# Vorladeschaltung.net
KiCad netlist of a schematic drawn in EAGLE
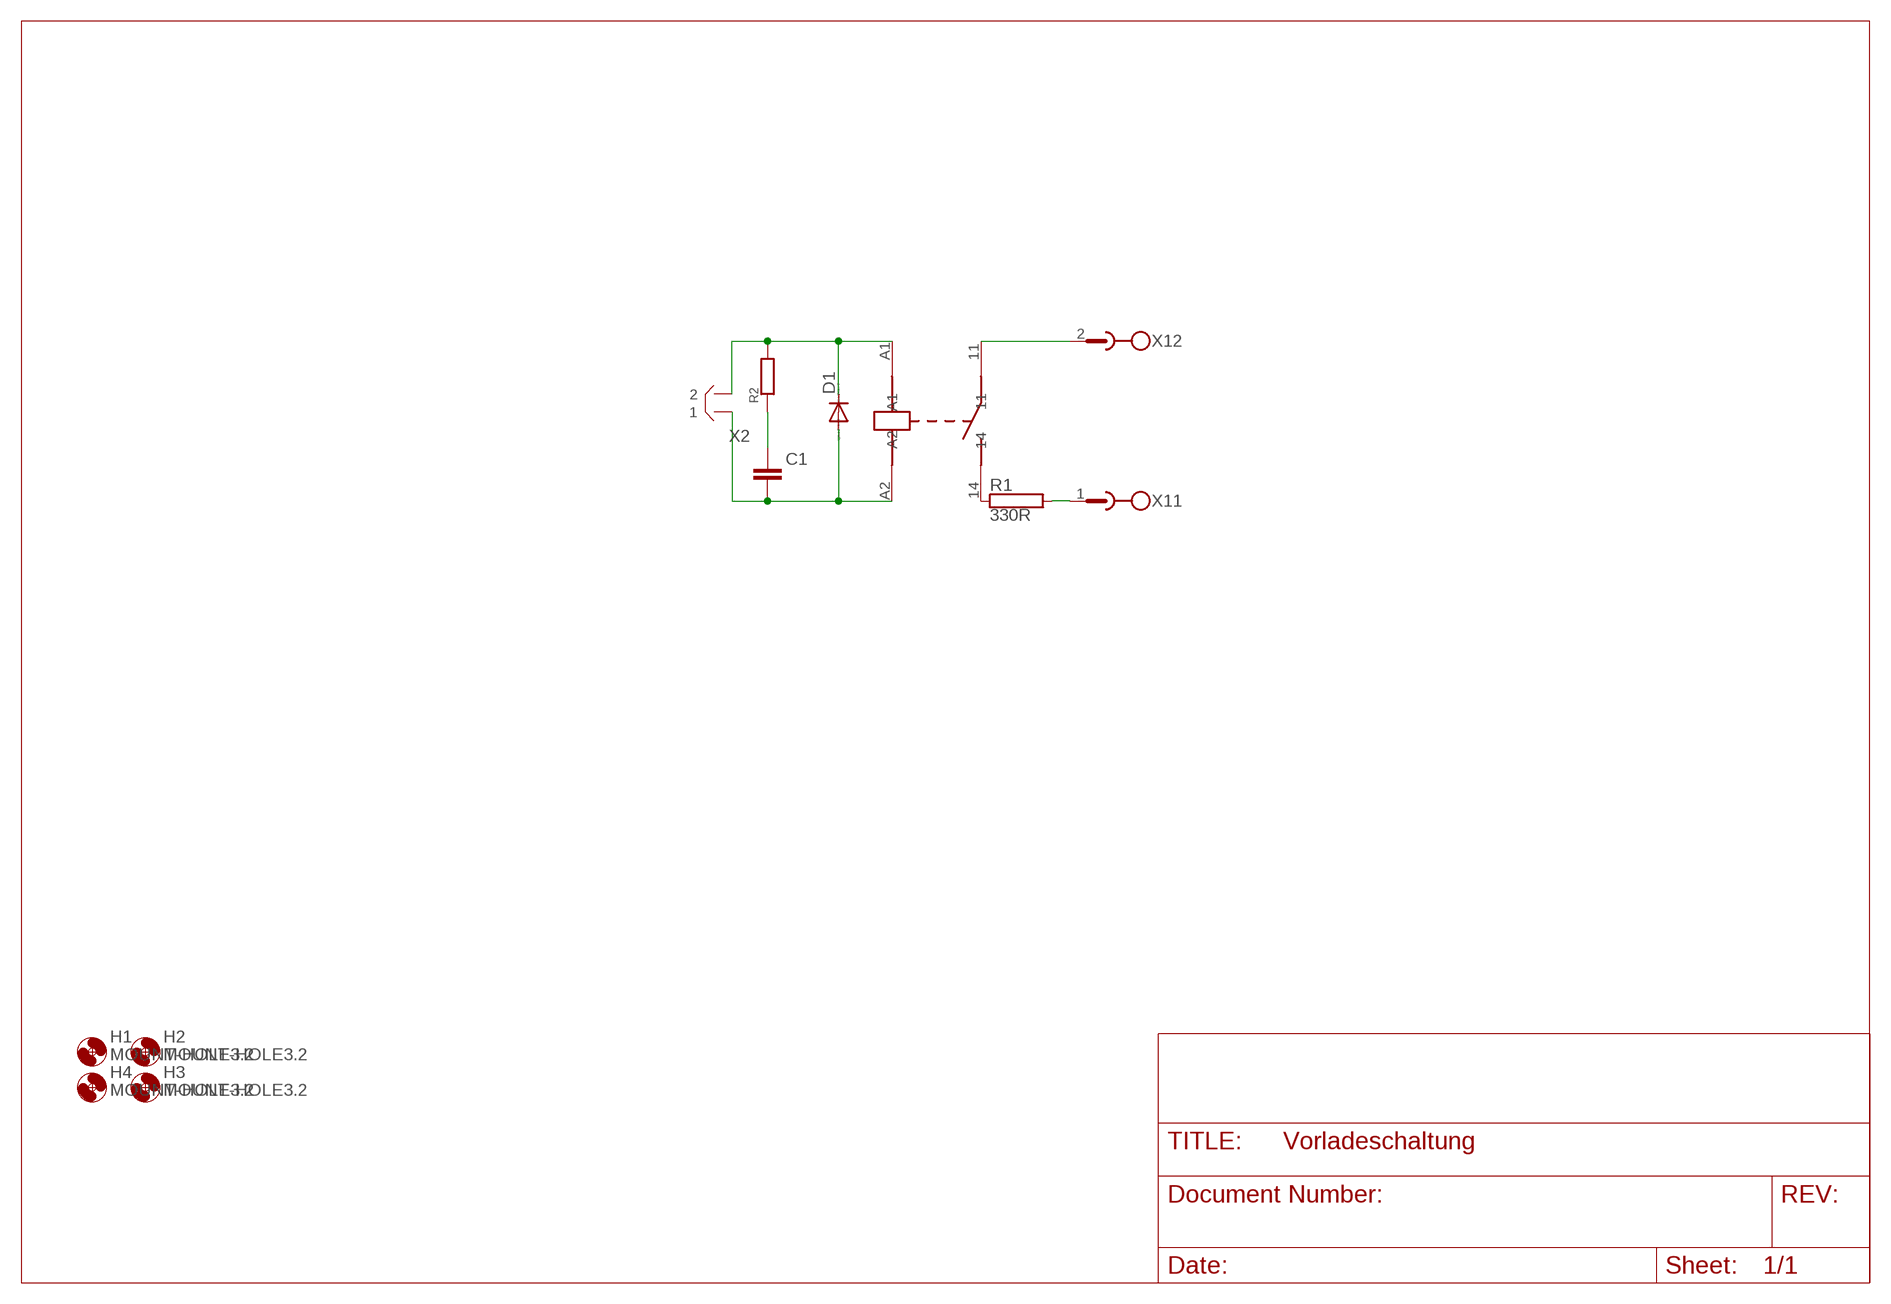
[diagram p0: schematic, sheet 1]

(export (version "E")
  (design (tool "Eeschema 10.0.6"))
  (components
    (comp (ref "C1")
      (value "CSTD")
      (footprint "eagle-import:C0805")
      (libsource (lib "eagle-import") (part "CSTD"))
    )
    (comp (ref "D1")
      (value "DIODE-SOD323-W")
      (footprint "eagle-import:SOD323-W")
      (libsource (lib "eagle-import") (part "DIODE-SOD323-W"))
    )
    (comp (ref "H1")
      (value "MOUNT-HOLE3.2")
      (footprint "eagle-import:3,2")
      (libsource (lib "eagle-import") (part "MOUNT-HOLE3.2"))
    )
    (comp (ref "H2")
      (value "MOUNT-HOLE3.2")
      (footprint "eagle-import:3,2")
      (libsource (lib "eagle-import") (part "MOUNT-HOLE3.2"))
    )
    (comp (ref "H3")
      (value "MOUNT-HOLE3.2")
      (footprint "eagle-import:3,2")
      (libsource (lib "eagle-import") (part "MOUNT-HOLE3.2"))
    )
    (comp (ref "H4")
      (value "MOUNT-HOLE3.2")
      (footprint "eagle-import:3,2")
      (libsource (lib "eagle-import") (part "MOUNT-HOLE3.2"))
    )
    (comp (ref "K1")
      (value "OJ-SH-112DMBIG")
      (footprint "eagle-import:RELAIS-TE-OJ-BIG")
      (libsource (lib "eagle-import") (part "OJ-SH-112DMBIG"))
    )
    (comp (ref "R1")
      (value "330R")
      (footprint "eagle-import:WH25")
      (libsource (lib "eagle-import") (part "RWH25"))
    )
    (comp (ref "R2")
      (value "R")
      (footprint "eagle-import:R0805")
      (libsource (lib "eagle-import") (part "useful_R"))
    )
    (comp (ref "X1")
      (value "MSTBX2MSTBA2")
      (footprint "eagle-import:MSTBA2")
      (libsource (lib "eagle-import") (part "MSTBX2MSTBA2"))
    )
    (comp (ref "X2")
      (value "B-BIG2B-XH")
      (footprint "eagle-import:B2B-XH-BIG")
      (libsource (lib "eagle-import") (part "?2B-XHB-BIG"))
    )
  )
  (nets
    (net (code "1") (name "Net-(C1-Pad2)") (class "Default")
      (node (ref "C1") (pin "2") (pinfunction "2_2") (pintype "passive"))
      (node (ref "R2") (pin "1") (pinfunction "1_1") (pintype "passive"))
    )
    (net (code "2") (name "Net-(K1-Pad14)") (class "Default")
      (node (ref "K1") (pin "14") (pinfunction "14_14") (pintype "bidirectional"))
      (node (ref "R1") (pin "1") (pinfunction "1_1") (pintype "passive"))
    )
    (net (code "3") (name "Net-(R1-Pad2)") (class "Default")
      (node (ref "R1") (pin "2") (pinfunction "2_2") (pintype "passive"))
      (node (ref "X1") (pin "1") (pinfunction "1_1") (pintype "passive"))
    )
    (net (code "4") (name "Net-(X1B-1)") (class "Default")
      (node (ref "K1") (pin "11") (pinfunction "11_11") (pintype "bidirectional"))
      (node (ref "X1") (pin "2") (pinfunction "1_2") (pintype "passive"))
    )
    (net (code "5") (name "Net-(X2-1)") (class "Default")
      (node (ref "C1") (pin "1") (pinfunction "1_1") (pintype "passive"))
      (node (ref "D1") (pin "A") (pinfunction "A_A") (pintype "passive"))
      (node (ref "K1") (pin "A2") (pinfunction "A2_A2") (pintype "bidirectional"))
      (node (ref "X2") (pin "P$1") (pinfunction "1_P$1") (pintype "bidirectional"))
    )
    (net (code "6") (name "Net-(X2-2)") (class "Default")
      (node (ref "D1") (pin "C") (pinfunction "C_C") (pintype "passive"))
      (node (ref "K1") (pin "A1") (pinfunction "A1_A1") (pintype "bidirectional"))
      (node (ref "R2") (pin "2") (pinfunction "2_2") (pintype "passive"))
      (node (ref "X2") (pin "P$2") (pinfunction "2_P$2") (pintype "bidirectional"))
    )
  )
)
